# 11_LMS1_Power.net
KiCad netlist of a schematic drawn in Altium Designer
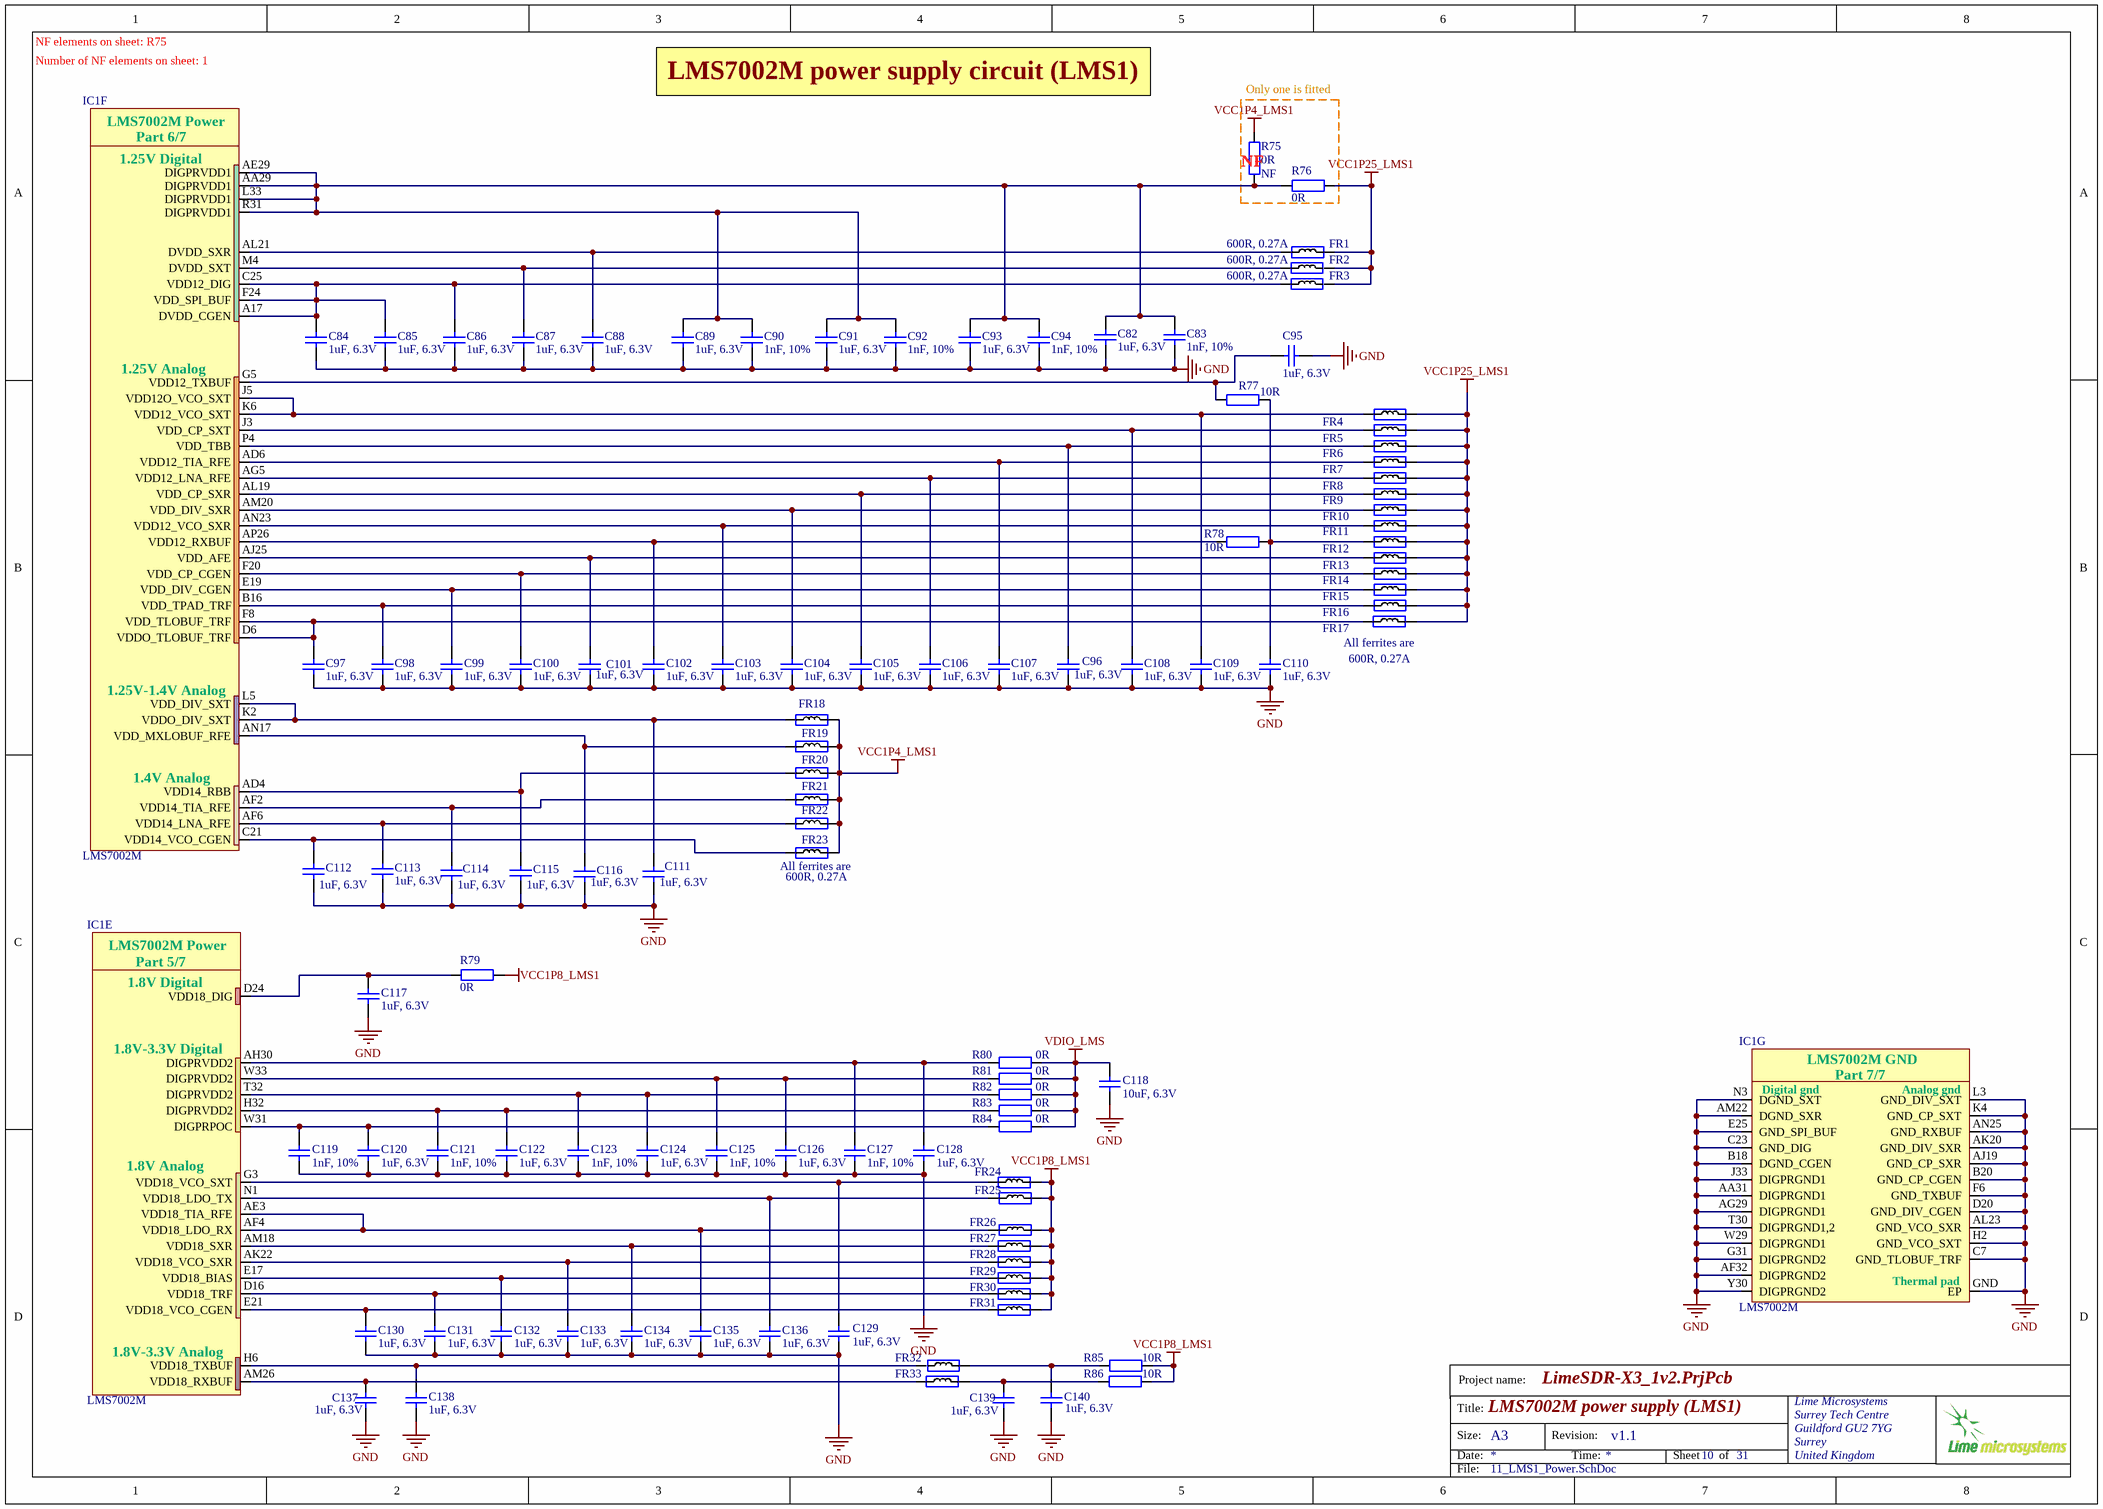
[diagram p0: 11_LMS1_Power.SchDoc]

(export (version "E")
  (design (tool "Eeschema 10.0.6"))
  (components
    (comp (ref "C82")
      (value "1uF, 6.3V")
      (footprint "CAP0201")
      (fields (field (name "TOLERANCE") "±20%") (field (name "MANUFACTURER") "TDK Corporation"))
      (libsource (lib "LimeMicroAltiumLib_schLib") (part "Cap_0402"))
    )
    (comp (ref "C83")
      (value "1nF, 10%")
      (footprint "CAP0201")
      (fields (field (name "TOLERANCE") "±10%") (field (name "MANUFACTURER") "TDK Corporation"))
      (libsource (lib "LimeMicroAltiumLib_schLib") (part "Cap_0402"))
    )
    (comp (ref "C84")
      (value "1uF, 6.3V")
      (footprint "CAP0201")
      (fields (field (name "TOLERANCE") "±20%") (field (name "MANUFACTURER") "TDK Corporation"))
      (libsource (lib "") (part "Cap_0402_1"))
    )
    (comp (ref "C85")
      (value "1uF, 6.3V")
      (footprint "CAP0201")
      (fields (field (name "TOLERANCE") "±20%") (field (name "MANUFACTURER") "TDK Corporation"))
      (libsource (lib "") (part "Cap_0402_1"))
    )
    (comp (ref "C86")
      (value "1uF, 6.3V")
      (footprint "CAP0201")
      (fields (field (name "TOLERANCE") "±20%") (field (name "MANUFACTURER") "TDK Corporation"))
      (libsource (lib "") (part "Cap_0402_1"))
    )
    (comp (ref "C87")
      (value "1uF, 6.3V")
      (footprint "CAP0201")
      (fields (field (name "TOLERANCE") "±20%") (field (name "MANUFACTURER") "TDK Corporation"))
      (libsource (lib "LimeMicroAltiumLib_schLib") (part "Cap_0402"))
    )
    (comp (ref "C88")
      (value "1uF, 6.3V")
      (footprint "CAP0201")
      (fields (field (name "TOLERANCE") "±20%") (field (name "MANUFACTURER") "TDK Corporation"))
      (libsource (lib "") (part "Cap_0402_1"))
    )
    (comp (ref "C89")
      (value "1uF, 6.3V")
      (footprint "CAP0201")
      (fields (field (name "TOLERANCE") "±20%") (field (name "MANUFACTURER") "TDK Corporation"))
      (libsource (lib "LimeMicroAltiumLib_schLib") (part "Cap_0402"))
    )
    (comp (ref "C90")
      (value "1nF, 10%")
      (footprint "CAP0201")
      (fields (field (name "TOLERANCE") "±10%") (field (name "MANUFACTURER") "TDK Corporation"))
      (libsource (lib "LimeMicroAltiumLib_schLib") (part "Cap_0402"))
    )
    (comp (ref "C91")
      (value "1uF, 6.3V")
      (footprint "CAP0201")
      (fields (field (name "TOLERANCE") "±20%") (field (name "MANUFACTURER") "TDK Corporation"))
      (libsource (lib "LimeMicroAltiumLib_schLib") (part "Cap_0402"))
    )
    (comp (ref "C92")
      (value "1nF, 10%")
      (footprint "CAP0201")
      (fields (field (name "TOLERANCE") "±10%") (field (name "MANUFACTURER") "TDK Corporation"))
      (libsource (lib "LimeMicroAltiumLib_schLib") (part "Cap_0402"))
    )
    (comp (ref "C93")
      (value "1uF, 6.3V")
      (footprint "CAP0201")
      (fields (field (name "TOLERANCE") "±20%") (field (name "MANUFACTURER") "TDK Corporation"))
      (libsource (lib "LimeMicroAltiumLib_schLib") (part "Cap_0402"))
    )
    (comp (ref "C94")
      (value "1nF, 10%")
      (footprint "CAP0201")
      (fields (field (name "TOLERANCE") "±10%") (field (name "MANUFACTURER") "TDK Corporation"))
      (libsource (lib "LimeMicroAltiumLib_schLib") (part "Cap_0402"))
    )
    (comp (ref "C95")
      (value "1uF, 6.3V")
      (footprint "CAP0201")
      (fields (field (name "TOLERANCE") "±20%") (field (name "MANUFACTURER") "TDK Corporation"))
      (libsource (lib "") (part "Cap_0402_4"))
    )
    (comp (ref "C96")
      (value "1uF, 6.3V")
      (footprint "CAP0201")
      (fields (field (name "TOLERANCE") "±20%") (field (name "MANUFACTURER") "TDK Corporation"))
      (libsource (lib "") (part "Cap_0402_1"))
    )
    (comp (ref "C97")
      (value "1uF, 6.3V")
      (footprint "CAP0201")
      (fields (field (name "TOLERANCE") "±20%") (field (name "MANUFACTURER") "TDK Corporation"))
      (libsource (lib "") (part "Cap_0402_1"))
    )
    (comp (ref "C98")
      (value "1uF, 6.3V")
      (footprint "CAP0201")
      (fields (field (name "TOLERANCE") "±20%") (field (name "MANUFACTURER") "TDK Corporation"))
      (libsource (lib "") (part "Cap_0402_1"))
    )
    (comp (ref "C99")
      (value "1uF, 6.3V")
      (footprint "CAP0201")
      (fields (field (name "TOLERANCE") "±20%") (field (name "MANUFACTURER") "TDK Corporation"))
      (libsource (lib "") (part "Cap_0402_1"))
    )
    (comp (ref "C100")
      (value "1uF, 6.3V")
      (footprint "CAP0201")
      (fields (field (name "TOLERANCE") "±20%") (field (name "MANUFACTURER") "TDK Corporation"))
      (libsource (lib "LimeMicroAltiumLib_schLib") (part "Cap_0402"))
    )
    (comp (ref "C101")
      (value "1uF, 6.3V")
      (footprint "CAP0201")
      (fields (field (name "TOLERANCE") "±20%") (field (name "MANUFACTURER") "TDK Corporation"))
      (libsource (lib "") (part "Cap_0402_1"))
    )
    (comp (ref "C102")
      (value "1uF, 6.3V")
      (footprint "CAP0201")
      (fields (field (name "TOLERANCE") "±20%") (field (name "MANUFACTURER") "TDK Corporation"))
      (libsource (lib "") (part "Cap_0402_1"))
    )
    (comp (ref "C103")
      (value "1uF, 6.3V")
      (footprint "CAP0201")
      (fields (field (name "TOLERANCE") "±20%") (field (name "MANUFACTURER") "TDK Corporation"))
      (libsource (lib "") (part "Cap_0402_1"))
    )
    (comp (ref "C104")
      (value "1uF, 6.3V")
      (footprint "CAP0201")
      (fields (field (name "TOLERANCE") "±20%") (field (name "MANUFACTURER") "TDK Corporation"))
      (libsource (lib "") (part "Cap_0402_1"))
    )
    (comp (ref "C105")
      (value "1uF, 6.3V")
      (footprint "CAP0201")
      (fields (field (name "TOLERANCE") "±20%") (field (name "MANUFACTURER") "TDK Corporation"))
      (libsource (lib "") (part "Cap_0402_1"))
    )
    (comp (ref "C106")
      (value "1uF, 6.3V")
      (footprint "CAP0201")
      (fields (field (name "TOLERANCE") "±20%") (field (name "MANUFACTURER") "TDK Corporation"))
      (libsource (lib "") (part "Cap_0402_1"))
    )
    (comp (ref "C107")
      (value "1uF, 6.3V")
      (footprint "CAP0201")
      (fields (field (name "TOLERANCE") "±20%") (field (name "MANUFACTURER") "TDK Corporation"))
      (libsource (lib "LimeMicroAltiumLib_schLib") (part "Cap_0402"))
    )
    (comp (ref "C108")
      (value "1uF, 6.3V")
      (footprint "CAP0201")
      (fields (field (name "TOLERANCE") "±20%") (field (name "MANUFACTURER") "TDK Corporation"))
      (libsource (lib "") (part "Cap_0402_1"))
    )
    (comp (ref "C109")
      (value "1uF, 6.3V")
      (footprint "CAP0201")
      (fields (field (name "TOLERANCE") "±20%") (field (name "MANUFACTURER") "TDK Corporation"))
      (libsource (lib "LimeMicroAltiumLib_schLib") (part "Cap_0402"))
    )
    (comp (ref "C110")
      (value "1uF, 6.3V")
      (footprint "CAP0201")
      (fields (field (name "TOLERANCE") "±20%") (field (name "MANUFACTURER") "TDK Corporation"))
      (libsource (lib "LimeMicroAltiumLib_schLib") (part "Cap_0402"))
    )
    (comp (ref "C111")
      (value "1uF, 6.3V")
      (footprint "CAP0201")
      (fields (field (name "TOLERANCE") "±20%") (field (name "MANUFACTURER") "TDK Corporation"))
      (libsource (lib "") (part "Cap_0402_1"))
    )
    (comp (ref "C112")
      (value "1uF, 6.3V")
      (footprint "CAP0201")
      (fields (field (name "TOLERANCE") "±20%") (field (name "MANUFACTURER") "TDK Corporation"))
      (libsource (lib "") (part "Cap_0402_1"))
    )
    (comp (ref "C113")
      (value "1uF, 6.3V")
      (footprint "CAP0201")
      (fields (field (name "TOLERANCE") "±20%") (field (name "MANUFACTURER") "TDK Corporation"))
      (libsource (lib "") (part "Cap_0402_1"))
    )
    (comp (ref "C114")
      (value "1uF, 6.3V")
      (footprint "CAP0201")
      (fields (field (name "TOLERANCE") "±20%") (field (name "MANUFACTURER") "TDK Corporation"))
      (libsource (lib "") (part "Cap_0402_2"))
    )
    (comp (ref "C115")
      (value "1uF, 6.3V")
      (footprint "CAP0201")
      (fields (field (name "TOLERANCE") "±20%") (field (name "MANUFACTURER") "TDK Corporation"))
      (libsource (lib "") (part "Cap_0402_2"))
    )
    (comp (ref "C116")
      (value "1uF, 6.3V")
      (footprint "CAP0201")
      (fields (field (name "TOLERANCE") "±20%") (field (name "MANUFACTURER") "TDK Corporation"))
      (libsource (lib "") (part "Cap_0402_1"))
    )
    (comp (ref "C117")
      (value "1uF, 6.3V")
      (footprint "CAP0201")
      (fields (field (name "TOLERANCE") "±20%") (field (name "MANUFACTURER") "TDK Corporation"))
      (libsource (lib "") (part "Cap_0402_3"))
    )
    (comp (ref "C118")
      (value "10uF, 6.3V")
      (footprint "CAP0603")
      (fields (field (name "TOLERANCE") "±20%") (field (name "MANUFACTURER") "Yageo"))
      (libsource (lib "LimeFPGAboard_schLib") (part "Cap_0603"))
    )
    (comp (ref "C119")
      (value "1nF, 10%")
      (footprint "CAP0201")
      (fields (field (name "TOLERANCE") "±10%") (field (name "MANUFACTURER") "TDK Corporation"))
      (libsource (lib "") (part "Cap_0402_3"))
    )
    (comp (ref "C120")
      (value "1uF, 6.3V")
      (footprint "CAP0201")
      (fields (field (name "TOLERANCE") "±20%") (field (name "MANUFACTURER") "TDK Corporation"))
      (libsource (lib "") (part "Cap_0402_3"))
    )
    (comp (ref "C121")
      (value "1nF, 10%")
      (footprint "CAP0201")
      (fields (field (name "TOLERANCE") "±10%") (field (name "MANUFACTURER") "TDK Corporation"))
      (libsource (lib "") (part "Cap_0402_3"))
    )
    (comp (ref "C122")
      (value "1uF, 6.3V")
      (footprint "CAP0201")
      (fields (field (name "TOLERANCE") "±20%") (field (name "MANUFACTURER") "TDK Corporation"))
      (libsource (lib "") (part "Cap_0402_3"))
    )
    (comp (ref "C123")
      (value "1nF, 10%")
      (footprint "CAP0201")
      (fields (field (name "TOLERANCE") "±10%") (field (name "MANUFACTURER") "TDK Corporation"))
      (libsource (lib "") (part "Cap_0402_3"))
    )
    (comp (ref "C124")
      (value "1uF, 6.3V")
      (footprint "CAP0201")
      (fields (field (name "TOLERANCE") "±20%") (field (name "MANUFACTURER") "TDK Corporation"))
      (libsource (lib "") (part "Cap_0402_3"))
    )
    (comp (ref "C125")
      (value "1nF, 10%")
      (footprint "CAP0201")
      (fields (field (name "TOLERANCE") "±10%") (field (name "MANUFACTURER") "TDK Corporation"))
      (libsource (lib "") (part "Cap_0402_3"))
    )
    (comp (ref "C126")
      (value "1uF, 6.3V")
      (footprint "CAP0201")
      (fields (field (name "TOLERANCE") "±20%") (field (name "MANUFACTURER") "TDK Corporation"))
      (libsource (lib "") (part "Cap_0402_3"))
    )
    (comp (ref "C127")
      (value "1nF, 10%")
      (footprint "CAP0201")
      (fields (field (name "TOLERANCE") "±10%") (field (name "MANUFACTURER") "TDK Corporation"))
      (libsource (lib "") (part "Cap_0402_3"))
    )
    (comp (ref "C128")
      (value "1uF, 6.3V")
      (footprint "CAP0201")
      (fields (field (name "TOLERANCE") "±20%") (field (name "MANUFACTURER") "TDK Corporation"))
      (libsource (lib "") (part "Cap_0402_3"))
    )
    (comp (ref "C129")
      (value "1uF, 6.3V")
      (footprint "CAP0201")
      (fields (field (name "TOLERANCE") "±20%") (field (name "MANUFACTURER") "TDK Corporation"))
      (libsource (lib "") (part "Cap_0402_3"))
    )
    (comp (ref "C130")
      (value "1uF, 6.3V")
      (footprint "CAP0201")
      (fields (field (name "TOLERANCE") "±20%") (field (name "MANUFACTURER") "TDK Corporation"))
      (libsource (lib "") (part "Cap_0402_3"))
    )
    (comp (ref "C131")
      (value "1uF, 6.3V")
      (footprint "CAP0201")
      (fields (field (name "TOLERANCE") "±20%") (field (name "MANUFACTURER") "TDK Corporation"))
      (libsource (lib "") (part "Cap_0402_3"))
    )
    (comp (ref "C132")
      (value "1uF, 6.3V")
      (footprint "CAP0201")
      (fields (field (name "TOLERANCE") "±20%") (field (name "MANUFACTURER") "TDK Corporation"))
      (libsource (lib "") (part "Cap_0402_3"))
    )
    (comp (ref "C133")
      (value "1uF, 6.3V")
      (footprint "CAP0201")
      (fields (field (name "TOLERANCE") "±20%") (field (name "MANUFACTURER") "TDK Corporation"))
      (libsource (lib "") (part "Cap_0402_3"))
    )
    (comp (ref "C134")
      (value "1uF, 6.3V")
      (footprint "CAP0201")
      (fields (field (name "TOLERANCE") "±20%") (field (name "MANUFACTURER") "TDK Corporation"))
      (libsource (lib "") (part "Cap_0402_3"))
    )
    (comp (ref "C135")
      (value "1uF, 6.3V")
      (footprint "CAP0201")
      (fields (field (name "TOLERANCE") "±20%") (field (name "MANUFACTURER") "TDK Corporation"))
      (libsource (lib "") (part "Cap_0402_3"))
    )
    (comp (ref "C136")
      (value "1uF, 6.3V")
      (footprint "CAP0201")
      (fields (field (name "TOLERANCE") "±20%") (field (name "MANUFACTURER") "TDK Corporation"))
      (libsource (lib "") (part "Cap_0402_3"))
    )
    (comp (ref "C137")
      (value "1uF, 6.3V")
      (footprint "CAP0201")
      (fields (field (name "TOLERANCE") "±20%") (field (name "MANUFACTURER") "TDK Corporation"))
      (libsource (lib "") (part "Cap_0402_3"))
    )
    (comp (ref "C138")
      (value "1uF, 6.3V")
      (footprint "CAP0201")
      (fields (field (name "TOLERANCE") "±20%") (field (name "MANUFACTURER") "TDK Corporation"))
      (libsource (lib "") (part "Cap_0402_3"))
    )
    (comp (ref "C139")
      (value "1uF, 6.3V")
      (footprint "CAP0201")
      (fields (field (name "TOLERANCE") "±20%") (field (name "MANUFACTURER") "TDK Corporation"))
      (libsource (lib "") (part "Cap_0402_3"))
    )
    (comp (ref "C140")
      (value "1uF, 6.3V")
      (footprint "CAP0201")
      (fields (field (name "TOLERANCE") "±20%") (field (name "MANUFACTURER") "TDK Corporation"))
      (libsource (lib "") (part "Cap_0402_3"))
    )
    (comp (ref "FR1")
      (value "600R, 0.27A")
      (footprint "RES0201")
      (fields (field (name "MANUFACTURER") "Taiyo Yuden"))
      (libsource (lib "") (part "Ferrite_2"))
    )
    (comp (ref "FR2")
      (value "600R, 0.27A")
      (footprint "RES0201")
      (fields (field (name "MANUFACTURER") "Taiyo Yuden"))
      (libsource (lib "LimeMicroAltiumLib_schLib") (part "Ferrite"))
    )
    (comp (ref "FR3")
      (value "600R, 0.27A")
      (footprint "RES0201")
      (fields (field (name "MANUFACTURER") "Taiyo Yuden"))
      (libsource (lib "LimeMicroAltiumLib_schLib") (part "Ferrite"))
    )
    (comp (ref "FR4")
      (value "600R, 0.27A")
      (footprint "RES0201")
      (fields (field (name "MANUFACTURER") "Taiyo Yuden"))
      (libsource (lib "") (part "Ferrite_2"))
    )
    (comp (ref "FR5")
      (value "600R, 0.27A")
      (footprint "RES0201")
      (fields (field (name "MANUFACTURER") "Taiyo Yuden"))
      (libsource (lib "") (part "Ferrite_2"))
    )
    (comp (ref "FR6")
      (value "600R, 0.27A")
      (footprint "RES0201")
      (fields (field (name "MANUFACTURER") "Taiyo Yuden"))
      (libsource (lib "") (part "Ferrite_2"))
    )
    (comp (ref "FR7")
      (value "600R, 0.27A")
      (footprint "RES0201")
      (fields (field (name "MANUFACTURER") "Taiyo Yuden"))
      (libsource (lib "") (part "Ferrite_2"))
    )
    (comp (ref "FR8")
      (value "600R, 0.27A")
      (footprint "RES0201")
      (fields (field (name "MANUFACTURER") "Taiyo Yuden"))
      (libsource (lib "") (part "Ferrite_2"))
    )
    (comp (ref "FR9")
      (value "600R, 0.27A")
      (footprint "RES0201")
      (fields (field (name "MANUFACTURER") "Taiyo Yuden"))
      (libsource (lib "") (part "Ferrite_2"))
    )
    (comp (ref "FR10")
      (value "600R, 0.27A")
      (footprint "RES0201")
      (fields (field (name "MANUFACTURER") "Taiyo Yuden"))
      (libsource (lib "") (part "Ferrite_2"))
    )
    (comp (ref "FR11")
      (value "600R, 0.27A")
      (footprint "RES0201")
      (fields (field (name "MANUFACTURER") "Taiyo Yuden"))
      (libsource (lib "") (part "Ferrite_2"))
    )
    (comp (ref "FR12")
      (value "600R, 0.27A")
      (footprint "RES0201")
      (fields (field (name "MANUFACTURER") "Taiyo Yuden"))
      (libsource (lib "") (part "Ferrite_2"))
    )
    (comp (ref "FR13")
      (value "600R, 0.27A")
      (footprint "RES0201")
      (fields (field (name "MANUFACTURER") "Taiyo Yuden"))
      (libsource (lib "") (part "Ferrite_2"))
    )
    (comp (ref "FR14")
      (value "600R, 0.27A")
      (footprint "RES0201")
      (fields (field (name "MANUFACTURER") "Taiyo Yuden"))
      (libsource (lib "") (part "Ferrite_2"))
    )
    (comp (ref "FR15")
      (value "600R, 0.27A")
      (footprint "RES0201")
      (fields (field (name "MANUFACTURER") "Taiyo Yuden"))
      (libsource (lib "") (part "Ferrite_2"))
    )
    (comp (ref "FR16")
      (value "600R, 0.27A")
      (footprint "RES0201")
      (fields (field (name "MANUFACTURER") "Taiyo Yuden"))
      (libsource (lib "") (part "Ferrite_2"))
    )
    (comp (ref "FR17")
      (value "600R, 0.27A")
      (footprint "RES0201")
      (fields (field (name "MANUFACTURER") "Taiyo Yuden"))
      (libsource (lib "LimeMicroAltiumLib_schLib") (part "Ferrite"))
    )
    (comp (ref "FR18")
      (value "600R, 0.27A")
      (footprint "RES0201")
      (fields (field (name "MANUFACTURER") "Taiyo Yuden"))
      (libsource (lib "LimeMicroAltiumLib_schLib") (part "Ferrite"))
    )
    (comp (ref "FR19")
      (value "600R, 0.27A")
      (footprint "RES0201")
      (fields (field (name "MANUFACTURER") "Taiyo Yuden"))
      (libsource (lib "LimeMicroAltiumLib_schLib") (part "Ferrite"))
    )
    (comp (ref "FR20")
      (value "600R, 0.27A")
      (footprint "RES0201")
      (fields (field (name "MANUFACTURER") "Taiyo Yuden"))
      (libsource (lib "LimeMicroAltiumLib_schLib") (part "Ferrite"))
    )
    (comp (ref "FR21")
      (value "600R, 0.27A")
      (footprint "RES0201")
      (fields (field (name "MANUFACTURER") "Taiyo Yuden"))
      (libsource (lib "LimeMicroAltiumLib_schLib") (part "Ferrite"))
    )
    (comp (ref "FR22")
      (value "600R, 0.27A")
      (footprint "RES0201")
      (fields (field (name "MANUFACTURER") "Taiyo Yuden"))
      (libsource (lib "LimeMicroAltiumLib_schLib") (part "Ferrite"))
    )
    (comp (ref "FR23")
      (value "600R, 0.27A")
      (footprint "RES0201")
      (fields (field (name "MANUFACTURER") "Taiyo Yuden"))
      (libsource (lib "LimeMicroAltiumLib_schLib") (part "Ferrite"))
    )
    (comp (ref "FR24")
      (value "600R, 0.27A")
      (footprint "RES0201")
      (fields (field (name "MANUFACTURER") "Taiyo Yuden"))
      (libsource (lib "LimeMicroAltiumLib_schLib") (part "Ferrite"))
    )
    (comp (ref "FR25")
      (value "600R, 0.27A")
      (footprint "RES0201")
      (fields (field (name "MANUFACTURER") "Taiyo Yuden"))
      (libsource (lib "") (part "Ferrite_1"))
    )
    (comp (ref "FR26")
      (value "600R, 0.27A")
      (footprint "RES0201")
      (fields (field (name "MANUFACTURER") "Taiyo Yuden"))
      (libsource (lib "") (part "Ferrite_1"))
    )
    (comp (ref "FR27")
      (value "600R, 0.27A")
      (footprint "RES0201")
      (fields (field (name "MANUFACTURER") "Taiyo Yuden"))
      (libsource (lib "LimeMicroAltiumLib_schLib") (part "Ferrite"))
    )
    (comp (ref "FR28")
      (value "600R, 0.27A")
      (footprint "RES0201")
      (fields (field (name "MANUFACTURER") "Taiyo Yuden"))
      (libsource (lib "LimeMicroAltiumLib_schLib") (part "Ferrite"))
    )
    (comp (ref "FR29")
      (value "600R, 0.27A")
      (footprint "RES0201")
      (fields (field (name "MANUFACTURER") "Taiyo Yuden"))
      (libsource (lib "LimeMicroAltiumLib_schLib") (part "Ferrite"))
    )
    (comp (ref "FR30")
      (value "600R, 0.27A")
      (footprint "RES0201")
      (fields (field (name "MANUFACTURER") "Taiyo Yuden"))
      (libsource (lib "LimeMicroAltiumLib_schLib") (part "Ferrite"))
    )
    (comp (ref "FR31")
      (value "600R, 0.27A")
      (footprint "RES0201")
      (fields (field (name "MANUFACTURER") "Taiyo Yuden"))
      (libsource (lib "LimeMicroAltiumLib_schLib") (part "Ferrite"))
    )
    (comp (ref "FR32")
      (value "600R, 0.27A")
      (footprint "RES0201")
      (fields (field (name "MANUFACTURER") "Taiyo Yuden"))
      (libsource (lib "") (part "Ferrite_1"))
    )
    (comp (ref "FR33")
      (value "600R, 0.27A")
      (footprint "RES0201")
      (fields (field (name "MANUFACTURER") "Taiyo Yuden"))
      (libsource (lib "LimeMicroAltiumLib_schLib") (part "Ferrite"))
    )
    (comp (ref "IC1")
      (value "LMS7002M")
      (footprint "LMS7002M_v5")
      (description "Schematic symbol revision 4. Default footprint - 0.31mm pad")
      (fields (field (name "MANUFACTURER") "Lime Microsystems"))
      (libsource (lib "LimeMicroAltiumLib_schLib_r04") (part "LMS7002Mr4"))
    )
    (comp (ref "R75")
      (value "0R")
      (footprint "RES0402")
      (fields
        (field (name "ASSEMBLY INFO") "NF")
        (field (name "MANUFACTURER") "Yageo")
        (field (name "TOLERANCE") "Jumper")
      )
      (libsource (lib "LimeMicroAltiumLib_schLib") (part "Res_0402"))
    )
    (comp (ref "R76")
      (value "0R")
      (footprint "RES0402")
      (fields (field (name "MANUFACTURER") "Yageo") (field (name "TOLERANCE") "Jumper"))
      (libsource (lib "") (part "Res_0402_1"))
    )
    (comp (ref "R77")
      (value "10R")
      (footprint "RES0201")
      (fields
        (field (name "MANUFACTURER") "Panasonic Electronic Components")
        (field (name "TOLERANCE") "±1%")
      )
      (libsource (lib "LimeMicroAltiumLib_schLib") (part "Res_0402"))
    )
    (comp (ref "R78")
      (value "10R")
      (footprint "RES0201")
      (fields
        (field (name "MANUFACTURER") "Panasonic Electronic Components")
        (field (name "TOLERANCE") "±1%")
      )
      (libsource (lib "LimeMicroAltiumLib_schLib") (part "Res_0402"))
    )
    (comp (ref "R79")
      (value "0R")
      (footprint "RES0201")
      (fields (field (name "MANUFACTURER") "Rohm Semiconductor") (field (name "TOLERANCE") "Jumper"))
      (libsource (lib "LimeMicroAltiumLib_schLib") (part "Res_0402"))
    )
    (comp (ref "R80")
      (value "0R")
      (footprint "RES0402")
      (fields (field (name "MANUFACTURER") "Yageo") (field (name "TOLERANCE") "Jumper"))
      (libsource (lib "LimeMicroAltiumLib_schLib") (part "Res_0402"))
    )
    (comp (ref "R81")
      (value "0R")
      (footprint "RES0402")
      (fields (field (name "MANUFACTURER") "Yageo") (field (name "TOLERANCE") "Jumper"))
      (libsource (lib "LimeMicroAltiumLib_schLib") (part "Res_0402"))
    )
    (comp (ref "R82")
      (value "0R")
      (footprint "RES0402")
      (fields (field (name "MANUFACTURER") "Yageo") (field (name "TOLERANCE") "Jumper"))
      (libsource (lib "LimeMicroAltiumLib_schLib") (part "Res_0402"))
    )
    (comp (ref "R83")
      (value "0R")
      (footprint "RES0402")
      (fields (field (name "MANUFACTURER") "Yageo") (field (name "TOLERANCE") "Jumper"))
      (libsource (lib "LimeMicroAltiumLib_schLib") (part "Res_0402"))
    )
    (comp (ref "R84")
      (value "0R")
      (footprint "RES0402")
      (fields (field (name "MANUFACTURER") "Yageo") (field (name "TOLERANCE") "Jumper"))
      (libsource (lib "LimeMicroAltiumLib_schLib") (part "Res_0402"))
    )
    (comp (ref "R85")
      (value "10R")
      (footprint "RES0201")
      (fields
        (field (name "MANUFACTURER") "Panasonic Electronic Components")
        (field (name "TOLERANCE") "±1%")
      )
      (libsource (lib "LimeMicroAltiumLib_schLib") (part "Res_0402"))
    )
    (comp (ref "R86")
      (value "10R")
      (footprint "RES0201")
      (fields
        (field (name "MANUFACTURER") "Panasonic Electronic Components")
        (field (name "TOLERANCE") "±1%")
      )
      (libsource (lib "LimeMicroAltiumLib_schLib") (part "Res_0402"))
    )
  )
  (nets
    (net (code "1") (name "GND") (class "Default")
      (node (ref "C100") (pin "1") (pinfunction "1_1") (pintype "passive"))
      (node (ref "C101") (pin "2") (pinfunction "2_2") (pintype "passive"))
      (node (ref "C102") (pin "2") (pinfunction "2_2") (pintype "passive"))
      (node (ref "C103") (pin "2") (pinfunction "2_2") (pintype "passive"))
      (node (ref "C104") (pin "2") (pinfunction "2_2") (pintype "passive"))
      (node (ref "C105") (pin "2") (pinfunction "2_2") (pintype "passive"))
      (node (ref "C106") (pin "2") (pinfunction "2_2") (pintype "passive"))
      (node (ref "C107") (pin "1") (pinfunction "1_1") (pintype "passive"))
      (node (ref "C108") (pin "2") (pinfunction "2_2") (pintype "passive"))
      (node (ref "C109") (pin "1") (pinfunction "1_1") (pintype "passive"))
      (node (ref "C110") (pin "1") (pinfunction "1_1") (pintype "passive"))
      (node (ref "C111") (pin "2") (pinfunction "2_2") (pintype "passive"))
      (node (ref "C112") (pin "2") (pinfunction "2_2") (pintype "passive"))
      (node (ref "C113") (pin "2") (pinfunction "2_2") (pintype "passive"))
      (node (ref "C114") (pin "2") (pinfunction "2_2") (pintype "passive"))
      (node (ref "C115") (pin "2") (pinfunction "2_2") (pintype "passive"))
      (node (ref "C116") (pin "2") (pinfunction "2_2") (pintype "passive"))
      (node (ref "C117") (pin "2") (pinfunction "2_2") (pintype "passive"))
      (node (ref "C118") (pin "1") (pinfunction "1_1") (pintype "passive"))
      (node (ref "C119") (pin "2") (pinfunction "2_2") (pintype "passive"))
      (node (ref "C120") (pin "2") (pinfunction "2_2") (pintype "passive"))
      (node (ref "C121") (pin "2") (pinfunction "2_2") (pintype "passive"))
      (node (ref "C122") (pin "2") (pinfunction "2_2") (pintype "passive"))
      (node (ref "C123") (pin "2") (pinfunction "2_2") (pintype "passive"))
      (node (ref "C124") (pin "2") (pinfunction "2_2") (pintype "passive"))
      (node (ref "C125") (pin "2") (pinfunction "2_2") (pintype "passive"))
      (node (ref "C126") (pin "2") (pinfunction "2_2") (pintype "passive"))
      (node (ref "C127") (pin "2") (pinfunction "2_2") (pintype "passive"))
      (node (ref "C128") (pin "2") (pinfunction "2_2") (pintype "passive"))
      (node (ref "C129") (pin "2") (pinfunction "2_2") (pintype "passive"))
      (node (ref "C130") (pin "2") (pinfunction "2_2") (pintype "passive"))
      (node (ref "C131") (pin "2") (pinfunction "2_2") (pintype "passive"))
      (node (ref "C132") (pin "2") (pinfunction "2_2") (pintype "passive"))
      (node (ref "C133") (pin "2") (pinfunction "2_2") (pintype "passive"))
      (node (ref "C134") (pin "2") (pinfunction "2_2") (pintype "passive"))
      (node (ref "C135") (pin "2") (pinfunction "2_2") (pintype "passive"))
      (node (ref "C136") (pin "2") (pinfunction "2_2") (pintype "passive"))
      (node (ref "C137") (pin "2") (pinfunction "2_2") (pintype "passive"))
      (node (ref "C138") (pin "2") (pinfunction "2_2") (pintype "passive"))
      (node (ref "C139") (pin "2") (pinfunction "2_2") (pintype "passive"))
      (node (ref "C140") (pin "2") (pinfunction "2_2") (pintype "passive"))
      (node (ref "C82") (pin "2") (pinfunction "2_2") (pintype "passive"))
      (node (ref "C83") (pin "2") (pinfunction "2_2") (pintype "passive"))
      (node (ref "C84") (pin "2") (pinfunction "2_2") (pintype "passive"))
      (node (ref "C85") (pin "2") (pinfunction "2_2") (pintype "passive"))
      (node (ref "C86") (pin "2") (pinfunction "2_2") (pintype "passive"))
      (node (ref "C87") (pin "1") (pinfunction "1_1") (pintype "passive"))
      (node (ref "C88") (pin "2") (pinfunction "2_2") (pintype "passive"))
      (node (ref "C89") (pin "2") (pinfunction "2_2") (pintype "passive"))
      (node (ref "C90") (pin "2") (pinfunction "2_2") (pintype "passive"))
      (node (ref "C91") (pin "2") (pinfunction "2_2") (pintype "passive"))
      (node (ref "C92") (pin "2") (pinfunction "2_2") (pintype "passive"))
      (node (ref "C93") (pin "2") (pinfunction "2_2") (pintype "passive"))
      (node (ref "C94") (pin "2") (pinfunction "2_2") (pintype "passive"))
      (node (ref "C95") (pin "2") (pinfunction "2_2") (pintype "passive"))
      (node (ref "C96") (pin "2") (pinfunction "2_2") (pintype "passive"))
      (node (ref "C97") (pin "2") (pinfunction "2_2") (pintype "passive"))
      (node (ref "C98") (pin "2") (pinfunction "2_2") (pintype "passive"))
      (node (ref "C99") (pin "2") (pinfunction "2_2") (pintype "passive"))
      (node (ref "IC1") (pin "AA31") (pinfunction "DIGPRGND1_AA31") (pintype "passive"))
      (node (ref "IC1") (pin "AF32") (pinfunction "DIGPRGND2_AF32") (pintype "passive"))
      (node (ref "IC1") (pin "AG29") (pinfunction "DIGPRGND1_AG29") (pintype "passive"))
      (node (ref "IC1") (pin "AJ19") (pinfunction "GND_CP_SXR_AJ19") (pintype "passive"))
      (node (ref "IC1") (pin "AK20") (pinfunction "GND_DIV_SXR_AK20") (pintype "passive"))
      (node (ref "IC1") (pin "AL23") (pinfunction "GND_VCO_SXR_AL23") (pintype "passive"))
      (node (ref "IC1") (pin "AM22") (pinfunction "DGND_SXR_AM22") (pintype "passive"))
      (node (ref "IC1") (pin "AN25") (pinfunction "GND_RXBUF_AN25") (pintype "passive"))
      (node (ref "IC1") (pin "B18") (pinfunction "DGND_CGEN_B18") (pintype "passive"))
      (node (ref "IC1") (pin "B20") (pinfunction "GND_CP_CGEN_B20") (pintype "passive"))
      (node (ref "IC1") (pin "C23") (pinfunction "GND_DIG_C23") (pintype "passive"))
      (node (ref "IC1") (pin "C7") (pinfunction "GND_TLOBUF_TRF_C7") (pintype "passive"))
      (node (ref "IC1") (pin "D20") (pinfunction "GND_DIV_CGEN_D20") (pintype "passive"))
      (node (ref "IC1") (pin "E25") (pinfunction "GND_SPI_BUF_E25") (pintype "passive"))
      (node (ref "IC1") (pin "F6") (pinfunction "GND_TXBUF_F6") (pintype "passive"))
      (node (ref "IC1") (pin "G31") (pinfunction "DIGPRGND2_G31") (pintype "passive"))
      (node (ref "IC1") (pin "GND") (pinfunction "EP_GND") (pintype "passive"))
      (node (ref "IC1") (pin "H2") (pinfunction "GND_VCO_SXT_H2") (pintype "passive"))
      (node (ref "IC1") (pin "J33") (pinfunction "DIGPRGND1_J33") (pintype "passive"))
      (node (ref "IC1") (pin "K4") (pinfunction "GND_CP_SXT_K4") (pintype "passive"))
      (node (ref "IC1") (pin "L3") (pinfunction "GND_DIV_SXT_L3") (pintype "passive"))
      (node (ref "IC1") (pin "N3") (pinfunction "DGND_SXT_N3") (pintype "passive"))
      (node (ref "IC1") (pin "T30") (pinfunction "DIGPRGND1,2_T30") (pintype "passive"))
      (node (ref "IC1") (pin "W29") (pinfunction "DIGPRGND1_W29") (pintype "passive"))
      (node (ref "IC1") (pin "Y30") (pinfunction "DIGPRGND2_Y30") (pintype "passive"))
    )
    (net (code "2") (name "Net-(C82-Pad1)") (class "Default")
      (node (ref "C82") (pin "1") (pinfunction "1_1") (pintype "passive"))
      (node (ref "C83") (pin "1") (pinfunction "1_1") (pintype "passive"))
      (node (ref "C89") (pin "1") (pinfunction "1_1") (pintype "passive"))
      (node (ref "C90") (pin "1") (pinfunction "1_1") (pintype "passive"))
      (node (ref "C91") (pin "1") (pinfunction "1_1") (pintype "passive"))
      (node (ref "C92") (pin "1") (pinfunction "1_1") (pintype "passive"))
      (node (ref "C93") (pin "1") (pinfunction "1_1") (pintype "passive"))
      (node (ref "C94") (pin "1") (pinfunction "1_1") (pintype "passive"))
      (node (ref "IC1") (pin "AA29") (pinfunction "DIGPRVDD1_AA29") (pintype "power_in"))
      (node (ref "IC1") (pin "AE29") (pinfunction "DIGPRVDD1_AE29") (pintype "power_in"))
      (node (ref "IC1") (pin "L33") (pinfunction "DIGPRVDD1_L33") (pintype "power_in"))
      (node (ref "IC1") (pin "R31") (pinfunction "DIGPRVDD1_R31") (pintype "power_in"))
      (node (ref "R75") (pin "2") (pinfunction "2_2") (pintype "passive"))
      (node (ref "R76") (pin "2") (pinfunction "2_2") (pintype "passive"))
    )
    (net (code "3") (name "Net-(C110-Pad2)") (class "Default")
      (node (ref "C110") (pin "2") (pinfunction "2_2") (pintype "passive"))
      (node (ref "FR12") (pin "1") (pinfunction "1_1") (pintype "passive"))
      (node (ref "R77") (pin "2") (pinfunction "2_2") (pintype "passive"))
      (node (ref "R78") (pin "2") (pinfunction "2_2") (pintype "passive"))
    )
    (net (code "4") (name "Net-(C121-Pad1)") (class "Default")
      (node (ref "C121") (pin "1") (pinfunction "1_1") (pintype "passive"))
      (node (ref "C122") (pin "1") (pinfunction "1_1") (pintype "passive"))
      (node (ref "IC1") (pin "H32") (pinfunction "DIGPRVDD2_H32") (pintype "power_in"))
      (node (ref "R83") (pin "2") (pinfunction "2_2") (pintype "passive"))
    )
    (net (code "5") (name "Net-(C123-Pad1)") (class "Default")
      (node (ref "C123") (pin "1") (pinfunction "1_1") (pintype "passive"))
      (node (ref "C124") (pin "1") (pinfunction "1_1") (pintype "passive"))
      (node (ref "IC1") (pin "T32") (pinfunction "DIGPRVDD2_T32") (pintype "power_in"))
      (node (ref "R82") (pin "2") (pinfunction "2_2") (pintype "passive"))
    )
    (net (code "6") (name "Net-(C125-Pad1)") (class "Default")
      (node (ref "C125") (pin "1") (pinfunction "1_1") (pintype "passive"))
      (node (ref "C126") (pin "1") (pinfunction "1_1") (pintype "passive"))
      (node (ref "IC1") (pin "W33") (pinfunction "DIGPRVDD2_W33") (pintype "power_in"))
      (node (ref "R81") (pin "2") (pinfunction "2_2") (pintype "passive"))
    )
    (net (code "7") (name "Net-(C127-Pad1)") (class "Default")
      (node (ref "C127") (pin "1") (pinfunction "1_1") (pintype "passive"))
      (node (ref "C128") (pin "1") (pinfunction "1_1") (pintype "passive"))
      (node (ref "IC1") (pin "AH30") (pinfunction "DIGPRVDD2_AH30") (pintype "power_in"))
      (node (ref "R80") (pin "2") (pinfunction "2_2") (pintype "passive"))
    )
    (net (code "8") (name "Net-(C139-Pad1)") (class "Default")
      (node (ref "C139") (pin "1") (pinfunction "1_1") (pintype "passive"))
      (node (ref "FR33") (pin "2") (pinfunction "2_2") (pintype "passive"))
      (node (ref "R86") (pin "2") (pinfunction "2_2") (pintype "passive"))
    )
    (net (code "9") (name "Net-(C140-Pad1)") (class "Default")
      (node (ref "C140") (pin "1") (pinfunction "1_1") (pintype "passive"))
      (node (ref "FR32") (pin "1") (pinfunction "1_1") (pintype "passive"))
      (node (ref "R85") (pin "1") (pinfunction "1_1") (pintype "passive"))
    )
    (net (code "10") (name "Net-(IC1E-DIGPRPOC)") (class "Default")
      (node (ref "C119") (pin "1") (pinfunction "1_1") (pintype "passive"))
      (node (ref "C120") (pin "1") (pinfunction "1_1") (pintype "passive"))
      (node (ref "IC1") (pin "W31") (pinfunction "DIGPRPOC_W31") (pintype "power_in"))
      (node (ref "R84") (pin "2") (pinfunction "2_2") (pintype "passive"))
    )
    (net (code "11") (name "Net-(IC1E-VDD18_BIAS)") (class "Default")
      (node (ref "C132") (pin "1") (pinfunction "1_1") (pintype "passive"))
      (node (ref "FR29") (pin "1") (pinfunction "1_1") (pintype "passive"))
      (node (ref "IC1") (pin "E17") (pinfunction "VDD18_BIAS_E17") (pintype "power_in"))
    )
    (net (code "12") (name "Net-(IC1E-VDD18_DIG)") (class "Default")
      (node (ref "C117") (pin "1") (pinfunction "1_1") (pintype "passive"))
      (node (ref "IC1") (pin "D24") (pinfunction "VDD18_DIG_D24") (pintype "power_in"))
      (node (ref "R79") (pin "1") (pinfunction "1_1") (pintype "passive"))
    )
    (net (code "13") (name "Net-(IC1E-VDD18_LDO_RX)") (class "Default")
      (node (ref "C135") (pin "1") (pinfunction "1_1") (pintype "passive"))
      (node (ref "FR26") (pin "2") (pinfunction "2_2") (pintype "passive"))
      (node (ref "IC1") (pin "AE3") (pinfunction "VDD18_TIA_RFE_AE3") (pintype "power_in"))
      (node (ref "IC1") (pin "AF4") (pinfunction "VDD18_LDO_RX_AF4") (pintype "power_in"))
    )
    (net (code "14") (name "Net-(IC1E-VDD18_LDO_TX)") (class "Default")
      (node (ref "C136") (pin "1") (pinfunction "1_1") (pintype "passive"))
      (node (ref "FR25") (pin "2") (pinfunction "2_2") (pintype "passive"))
      (node (ref "IC1") (pin "N1") (pinfunction "VDD18_LDO_TX_N1") (pintype "power_in"))
    )
    (net (code "15") (name "Net-(IC1E-VDD18_RXBUF)") (class "Default")
      (node (ref "C137") (pin "1") (pinfunction "1_1") (pintype "passive"))
      (node (ref "FR33") (pin "1") (pinfunction "1_1") (pintype "passive"))
      (node (ref "IC1") (pin "AM26") (pinfunction "VDD18_RXBUF_AM26") (pintype "power_in"))
    )
    (net (code "16") (name "Net-(IC1E-VDD18_SXR)") (class "Default")
      (node (ref "C134") (pin "1") (pinfunction "1_1") (pintype "passive"))
      (node (ref "FR27") (pin "1") (pinfunction "1_1") (pintype "passive"))
      (node (ref "IC1") (pin "AM18") (pinfunction "VDD18_SXR_AM18") (pintype "power_in"))
    )
    (net (code "17") (name "Net-(IC1E-VDD18_TRF)") (class "Default")
      (node (ref "C131") (pin "1") (pinfunction "1_1") (pintype "passive"))
      (node (ref "FR30") (pin "1") (pinfunction "1_1") (pintype "passive"))
      (node (ref "IC1") (pin "D16") (pinfunction "VDD18_TRF_D16") (pintype "power_in"))
    )
    (net (code "18") (name "Net-(IC1E-VDD18_TXBUF)") (class "Default")
      (node (ref "C138") (pin "1") (pinfunction "1_1") (pintype "passive"))
      (node (ref "FR32") (pin "2") (pinfunction "2_2") (pintype "passive"))
      (node (ref "IC1") (pin "H6") (pinfunction "VDD18_TXBUF_H6") (pintype "power_in"))
    )
    (net (code "19") (name "Net-(IC1E-VDD18_VCO_CGEN)") (class "Default")
      (node (ref "C130") (pin "1") (pinfunction "1_1") (pintype "passive"))
      (node (ref "FR31") (pin "1") (pinfunction "1_1") (pintype "passive"))
      (node (ref "IC1") (pin "E21") (pinfunction "VDD18_VCO_CGEN_E21") (pintype "power_in"))
    )
    (net (code "20") (name "Net-(IC1E-VDD18_VCO_SXR)") (class "Default")
      (node (ref "C133") (pin "1") (pinfunction "1_1") (pintype "passive"))
      (node (ref "FR28") (pin "1") (pinfunction "1_1") (pintype "passive"))
      (node (ref "IC1") (pin "AK22") (pinfunction "VDD18_VCO_SXR_AK22") (pintype "power_in"))
    )
    (net (code "21") (name "Net-(IC1E-VDD18_VCO_SXT)") (class "Default")
      (node (ref "C129") (pin "1") (pinfunction "1_1") (pintype "passive"))
      (node (ref "FR24") (pin "1") (pinfunction "1_1") (pintype "passive"))
      (node (ref "IC1") (pin "G3") (pinfunction "VDD18_VCO_SXT_G3") (pintype "power_in"))
    )
    (net (code "22") (name "Net-(IC1F-DVDD_CGEN)") (class "Default")
      (node (ref "C84") (pin "1") (pinfunction "1_1") (pintype "passive"))
      (node (ref "C85") (pin "1") (pinfunction "1_1") (pintype "passive"))
      (node (ref "C86") (pin "1") (pinfunction "1_1") (pintype "passive"))
      (node (ref "FR3") (pin "1") (pinfunction "1_1") (pintype "passive"))
      (node (ref "IC1") (pin "A17") (pinfunction "DVDD_CGEN_A17") (pintype "power_in"))
      (node (ref "IC1") (pin "C25") (pinfunction "VDD12_DIG_C25") (pintype "power_in"))
      (node (ref "IC1") (pin "F24") (pinfunction "VDD_SPI_BUF_F24") (pintype "power_in"))
    )
    (net (code "23") (name "Net-(IC1F-DVDD_SXR)") (class "Default")
      (node (ref "C88") (pin "1") (pinfunction "1_1") (pintype "passive"))
      (node (ref "FR1") (pin "1") (pinfunction "1_1") (pintype "passive"))
      (node (ref "IC1") (pin "AL21") (pinfunction "DVDD_SXR_AL21") (pintype "power_in"))
    )
    (net (code "24") (name "Net-(IC1F-DVDD_SXT)") (class "Default")
      (node (ref "C87") (pin "2") (pinfunction "2_2") (pintype "passive"))
      (node (ref "FR2") (pin "1") (pinfunction "1_1") (pintype "passive"))
      (node (ref "IC1") (pin "M4") (pinfunction "DVDD_SXT_M4") (pintype "power_in"))
    )
    (net (code "25") (name "Net-(IC1F-VDD12O_VCO_SXT)") (class "Default")
      (node (ref "C109") (pin "2") (pinfunction "2_2") (pintype "passive"))
      (node (ref "FR4") (pin "1") (pinfunction "1_1") (pintype "passive"))
      (node (ref "IC1") (pin "J5") (pinfunction "VDD12O_VCO_SXT_J5") (pintype "power_in"))
      (node (ref "IC1") (pin "K6") (pinfunction "VDD12_VCO_SXT_K6") (pintype "power_in"))
    )
    (net (code "26") (name "Net-(IC1F-VDD12_LNA_RFE)") (class "Default")
      (node (ref "C106") (pin "1") (pinfunction "1_1") (pintype "passive"))
      (node (ref "FR8") (pin "1") (pinfunction "1_1") (pintype "passive"))
      (node (ref "IC1") (pin "AG5") (pinfunction "VDD12_LNA_RFE_AG5") (pintype "power_in"))
    )
    (net (code "27") (name "Net-(IC1F-VDD12_RXBUF)") (class "Default")
      (node (ref "C102") (pin "1") (pinfunction "1_1") (pintype "passive"))
      (node (ref "IC1") (pin "AP26") (pinfunction "VDD12_RXBUF_AP26") (pintype "power_in"))
      (node (ref "R78") (pin "1") (pinfunction "1_1") (pintype "passive"))
    )
    (net (code "28") (name "Net-(IC1F-VDD12_TIA_RFE)") (class "Default")
      (node (ref "C107") (pin "2") (pinfunction "2_2") (pintype "passive"))
      (node (ref "FR7") (pin "1") (pinfunction "1_1") (pintype "passive"))
      (node (ref "IC1") (pin "AD6") (pinfunction "VDD12_TIA_RFE_AD6") (pintype "power_in"))
    )
    (net (code "29") (name "Net-(IC1F-VDD12_TXBUF)") (class "Default")
      (node (ref "C95") (pin "1") (pinfunction "1_1") (pintype "passive"))
      (node (ref "IC1") (pin "G5") (pinfunction "VDD12_TXBUF_G5") (pintype "power_in"))
      (node (ref "R77") (pin "1") (pinfunction "1_1") (pintype "passive"))
    )
    (net (code "30") (name "Net-(IC1F-VDD12_VCO_SXR)") (class "Default")
      (node (ref "C103") (pin "1") (pinfunction "1_1") (pintype "passive"))
      (node (ref "FR11") (pin "1") (pinfunction "1_1") (pintype "passive"))
      (node (ref "IC1") (pin "AN23") (pinfunction "VDD12_VCO_SXR_AN23") (pintype "power_in"))
    )
    (net (code "31") (name "Net-(IC1F-VDD14_LNA_RFE)") (class "Default")
      (node (ref "C113") (pin "1") (pinfunction "1_1") (pintype "passive"))
      (node (ref "FR22") (pin "1") (pinfunction "1_1") (pintype "passive"))
      (node (ref "IC1") (pin "AF6") (pinfunction "VDD14_LNA_RFE_AF6") (pintype "power_in"))
    )
    (net (code "32") (name "Net-(IC1F-VDD14_RBB)") (class "Default")
      (node (ref "C115") (pin "1") (pinfunction "1_1") (pintype "passive"))
      (node (ref "FR20") (pin "1") (pinfunction "1_1") (pintype "passive"))
      (node (ref "IC1") (pin "AD4") (pinfunction "VDD14_RBB_AD4") (pintype "power_in"))
    )
    (net (code "33") (name "Net-(IC1F-VDD14_TIA_RFE)") (class "Default")
      (node (ref "C114") (pin "1") (pinfunction "1_1") (pintype "passive"))
      (node (ref "FR21") (pin "1") (pinfunction "1_1") (pintype "passive"))
      (node (ref "IC1") (pin "AF2") (pinfunction "VDD14_TIA_RFE_AF2") (pintype "power_in"))
    )
    (net (code "34") (name "Net-(IC1F-VDD14_VCO_CGEN)") (class "Default")
      (node (ref "C112") (pin "1") (pinfunction "1_1") (pintype "passive"))
      (node (ref "FR23") (pin "1") (pinfunction "1_1") (pintype "passive"))
      (node (ref "IC1") (pin "C21") (pinfunction "VDD14_VCO_CGEN_C21") (pintype "power_in"))
    )
    (net (code "35") (name "Net-(IC1F-VDDO_DIV_SXT)") (class "Default")
      (node (ref "C111") (pin "1") (pinfunction "1_1") (pintype "passive"))
      (node (ref "FR18") (pin "1") (pinfunction "1_1") (pintype "passive"))
      (node (ref "IC1") (pin "K2") (pinfunction "VDDO_DIV_SXT_K2") (pintype "power_in"))
      (node (ref "IC1") (pin "L5") (pinfunction "VDD_DIV_SXT_L5") (pintype "power_in"))
    )
    (net (code "36") (name "Net-(IC1F-VDDO_TLOBUF_TRF)") (class "Default")
      (node (ref "C97") (pin "1") (pinfunction "1_1") (pintype "passive"))
      (node (ref "FR17") (pin "1") (pinfunction "1_1") (pintype "passive"))
      (node (ref "IC1") (pin "D6") (pinfunction "VDDO_TLOBUF_TRF_D6") (pintype "power_in"))
      (node (ref "IC1") (pin "F8") (pinfunction "VDD_TLOBUF_TRF_F8") (pintype "power_in"))
    )
    (net (code "37") (name "Net-(IC1F-VDD_AFE)") (class "Default")
      (node (ref "C101") (pin "1") (pinfunction "1_1") (pintype "passive"))
      (node (ref "FR13") (pin "1") (pinfunction "1_1") (pintype "passive"))
      (node (ref "IC1") (pin "AJ25") (pinfunction "VDD_AFE_AJ25") (pintype "power_in"))
    )
    (net (code "38") (name "Net-(IC1F-VDD_CP_CGEN)") (class "Default")
      (node (ref "C100") (pin "2") (pinfunction "2_2") (pintype "passive"))
      (node (ref "FR14") (pin "1") (pinfunction "1_1") (pintype "passive"))
      (node (ref "IC1") (pin "F20") (pinfunction "VDD_CP_CGEN_F20") (pintype "power_in"))
    )
    (net (code "39") (name "Net-(IC1F-VDD_CP_SXR)") (class "Default")
      (node (ref "C105") (pin "1") (pinfunction "1_1") (pintype "passive"))
      (node (ref "FR9") (pin "1") (pinfunction "1_1") (pintype "passive"))
      (node (ref "IC1") (pin "AL19") (pinfunction "VDD_CP_SXR_AL19") (pintype "power_in"))
    )
    (net (code "40") (name "Net-(IC1F-VDD_CP_SXT)") (class "Default")
      (node (ref "C108") (pin "1") (pinfunction "1_1") (pintype "passive"))
      (node (ref "FR5") (pin "1") (pinfunction "1_1") (pintype "passive"))
      (node (ref "IC1") (pin "J3") (pinfunction "VDD_CP_SXT_J3") (pintype "power_in"))
    )
    (net (code "41") (name "Net-(IC1F-VDD_DIV_CGEN)") (class "Default")
      (node (ref "C99") (pin "1") (pinfunction "1_1") (pintype "passive"))
      (node (ref "FR15") (pin "1") (pinfunction "1_1") (pintype "passive"))
      (node (ref "IC1") (pin "E19") (pinfunction "VDD_DIV_CGEN_E19") (pintype "power_in"))
    )
    (net (code "42") (name "Net-(IC1F-VDD_DIV_SXR)") (class "Default")
      (node (ref "C104") (pin "1") (pinfunction "1_1") (pintype "passive"))
      (node (ref "FR10") (pin "1") (pinfunction "1_1") (pintype "passive"))
      (node (ref "IC1") (pin "AM20") (pinfunction "VDD_DIV_SXR_AM20") (pintype "power_in"))
    )
    (net (code "43") (name "Net-(IC1F-VDD_MXLOBUF_RFE)") (class "Default")
      (node (ref "C116") (pin "1") (pinfunction "1_1") (pintype "passive"))
      (node (ref "FR19") (pin "1") (pinfunction "1_1") (pintype "passive"))
      (node (ref "IC1") (pin "AN17") (pinfunction "VDD_MXLOBUF_RFE_AN17") (pintype "power_in"))
    )
    (net (code "44") (name "Net-(IC1F-VDD_TBB)") (class "Default")
      (node (ref "C96") (pin "1") (pinfunction "1_1") (pintype "passive"))
      (node (ref "FR6") (pin "1") (pinfunction "1_1") (pintype "passive"))
      (node (ref "IC1") (pin "P4") (pinfunction "VDD_TBB_P4") (pintype "power_in"))
    )
    (net (code "45") (name "Net-(IC1F-VDD_TPAD_TRF)") (class "Default")
      (node (ref "C98") (pin "1") (pinfunction "1_1") (pintype "passive"))
      (node (ref "FR16") (pin "1") (pinfunction "1_1") (pintype "passive"))
      (node (ref "IC1") (pin "B16") (pinfunction "VDD_TPAD_TRF_B16") (pintype "power_in"))
    )
    (net (code "46") (name "VCC1P4_LMS1") (class "Default")
      (node (ref "FR18") (pin "2") (pinfunction "2_2") (pintype "passive"))
      (node (ref "FR19") (pin "2") (pinfunction "2_2") (pintype "passive"))
      (node (ref "FR20") (pin "2") (pinfunction "2_2") (pintype "passive"))
      (node (ref "FR21") (pin "2") (pinfunction "2_2") (pintype "passive"))
      (node (ref "FR22") (pin "2") (pinfunction "2_2") (pintype "passive"))
      (node (ref "FR23") (pin "2") (pinfunction "2_2") (pintype "passive"))
      (node (ref "R75") (pin "1") (pinfunction "1_1") (pintype "passive"))
    )
    (net (code "47") (name "VCC1P8_LMS1") (class "Default")
      (node (ref "FR24") (pin "2") (pinfunction "2_2") (pintype "passive"))
      (node (ref "FR25") (pin "1") (pinfunction "1_1") (pintype "passive"))
      (node (ref "FR26") (pin "1") (pinfunction "1_1") (pintype "passive"))
      (node (ref "FR27") (pin "2") (pinfunction "2_2") (pintype "passive"))
      (node (ref "FR28") (pin "2") (pinfunction "2_2") (pintype "passive"))
      (node (ref "FR29") (pin "2") (pinfunction "2_2") (pintype "passive"))
      (node (ref "FR30") (pin "2") (pinfunction "2_2") (pintype "passive"))
      (node (ref "FR31") (pin "2") (pinfunction "2_2") (pintype "passive"))
      (node (ref "R79") (pin "2") (pinfunction "2_2") (pintype "passive"))
      (node (ref "R85") (pin "2") (pinfunction "2_2") (pintype "passive"))
      (node (ref "R86") (pin "1") (pinfunction "1_1") (pintype "passive"))
    )
    (net (code "48") (name "VCC1P25_LMS1") (class "Default")
      (node (ref "FR1") (pin "2") (pinfunction "2_2") (pintype "passive"))
      (node (ref "FR10") (pin "2") (pinfunction "2_2") (pintype "passive"))
      (node (ref "FR11") (pin "2") (pinfunction "2_2") (pintype "passive"))
      (node (ref "FR12") (pin "2") (pinfunction "2_2") (pintype "passive"))
      (node (ref "FR13") (pin "2") (pinfunction "2_2") (pintype "passive"))
      (node (ref "FR14") (pin "2") (pinfunction "2_2") (pintype "passive"))
      (node (ref "FR15") (pin "2") (pinfunction "2_2") (pintype "passive"))
      (node (ref "FR16") (pin "2") (pinfunction "2_2") (pintype "passive"))
      (node (ref "FR17") (pin "2") (pinfunction "2_2") (pintype "passive"))
      (node (ref "FR2") (pin "2") (pinfunction "2_2") (pintype "passive"))
      (node (ref "FR3") (pin "2") (pinfunction "2_2") (pintype "passive"))
      (node (ref "FR4") (pin "2") (pinfunction "2_2") (pintype "passive"))
      (node (ref "FR5") (pin "2") (pinfunction "2_2") (pintype "passive"))
      (node (ref "FR6") (pin "2") (pinfunction "2_2") (pintype "passive"))
      (node (ref "FR7") (pin "2") (pinfunction "2_2") (pintype "passive"))
      (node (ref "FR8") (pin "2") (pinfunction "2_2") (pintype "passive"))
      (node (ref "FR9") (pin "2") (pinfunction "2_2") (pintype "passive"))
      (node (ref "R76") (pin "1") (pinfunction "1_1") (pintype "passive"))
    )
    (net (code "49") (name "VDIO_LMS") (class "Default")
      (node (ref "C118") (pin "2") (pinfunction "2_2") (pintype "passive"))
      (node (ref "R80") (pin "1") (pinfunction "1_1") (pintype "passive"))
      (node (ref "R81") (pin "1") (pinfunction "1_1") (pintype "passive"))
      (node (ref "R82") (pin "1") (pinfunction "1_1") (pintype "passive"))
      (node (ref "R83") (pin "1") (pinfunction "1_1") (pintype "passive"))
      (node (ref "R84") (pin "1") (pinfunction "1_1") (pintype "passive"))
    )
  )
)
